# ST_LINK_V3E.net
KiCad netlist of a schematic drawn in Altium Designer
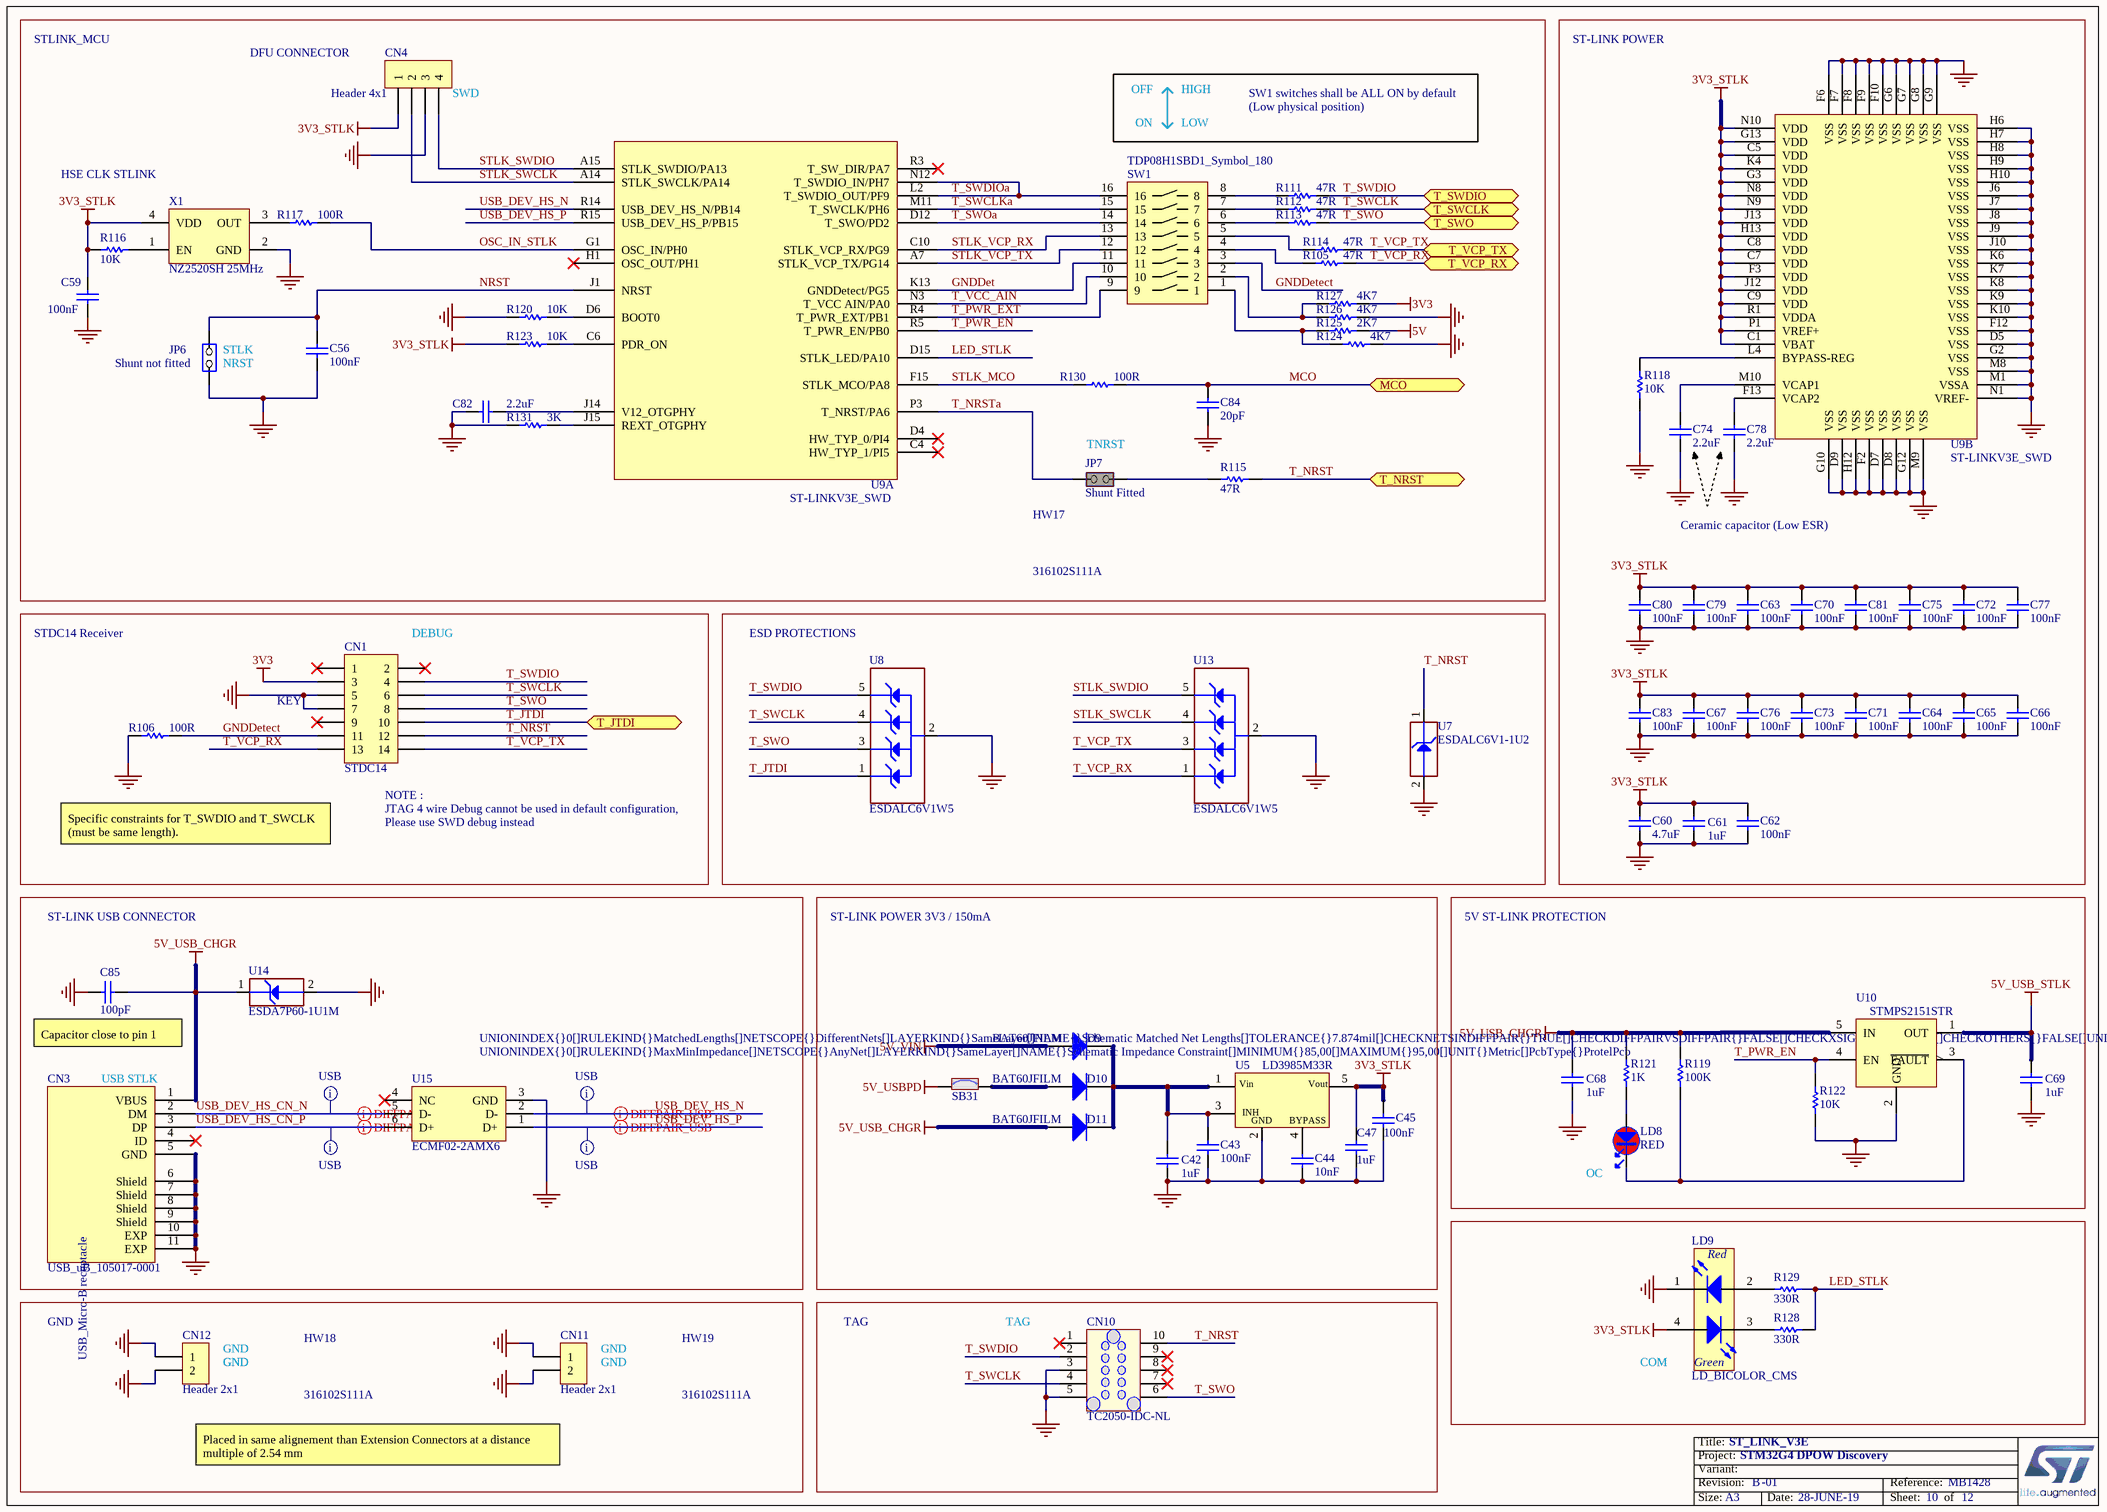
[diagram p0: ST_LINK_V3E.SchDoc]

(export (version "E")
  (design (tool "Eeschema 10.0.6"))
  (components
    (comp (ref "C42")
      (value "1uF")
      (footprint "C0603")
      (description "Capacitor, MLCC, 1uF, 16V, X5R, 10%, 0603, T=0,8mm")
      (fields
        (field (name "INTERNAL_PART_NUMBER") "MCD-00010")
        (field (name "MANUFACTURER_PART_NUMBER") "CC0603KRX5R7BB105")
        (field (name "PROVIDED_BY") "SUBCO")
      )
      (libsource (lib "MCD_PARTS_database") (part "Capacitor"))
    )
    (comp (ref "C43")
      (value "100nF")
      (footprint "C0402")
      (description "Capacitor, MLCC, 100nF, 16V, X7R, 10%, 0402, T=0,5mm")
      (fields
        (field (name "INTERNAL_PART_NUMBER") "MCD-00102")
        (field (name "MANUFACTURER_PART_NUMBER") "CC0402KRX7R7BB104")
        (field (name "PROVIDED_BY") "SUBCO")
      )
      (libsource (lib "MCD_PARTS_database") (part "Capacitor"))
    )
    (comp (ref "C44")
      (value "10nF")
      (footprint "C0402")
      (description "Capacitor, MLCC, 10nF, 16V, X7R, 10%, 0402, T=0.5mm")
      (fields
        (field (name "INTERNAL_PART_NUMBER") "MCD-00011")
        (field (name "MANUFACTURER_PART_NUMBER") "CC0402KRX7R7BB103")
        (field (name "PROVIDED_BY") "SUBCO")
      )
      (libsource (lib "MCD_PARTS_database") (part "Capacitor"))
    )
    (comp (ref "C45")
      (value "100nF")
      (footprint "C0402")
      (description "Capacitor, MLCC, 100nF, 16V, X7R, 10%, 0402, T=0,5mm")
      (fields
        (field (name "INTERNAL_PART_NUMBER") "MCD-00102")
        (field (name "MANUFACTURER_PART_NUMBER") "CC0402KRX7R7BB104")
        (field (name "PROVIDED_BY") "SUBCO")
      )
      (libsource (lib "MCD_PARTS_database") (part "Capacitor"))
    )
    (comp (ref "C47")
      (value "1uF")
      (footprint "C0603")
      (description "Capacitor, MLCC, 1uF, 16V, X5R, 10%, 0603, T=0,8mm")
      (fields
        (field (name "INTERNAL_PART_NUMBER") "MCD-00010")
        (field (name "MANUFACTURER_PART_NUMBER") "CC0603KRX5R7BB105")
        (field (name "PROVIDED_BY") "SUBCO")
      )
      (libsource (lib "MCD_PARTS_database") (part "Capacitor"))
    )
    (comp (ref "C56")
      (value "100nF")
      (footprint "C0402")
      (description "Capacitor, MLCC, 100nF, 16V, X7R, 10%, 0402, T=0,5mm")
      (fields
        (field (name "INTERNAL_PART_NUMBER") "MCD-00102")
        (field (name "MANUFACTURER_PART_NUMBER") "CC0402KRX7R7BB104")
        (field (name "PROVIDED_BY") "SUBCO")
      )
      (libsource (lib "MCD_PARTS_database") (part "Capacitor"))
    )
    (comp (ref "C59")
      (value "100nF")
      (footprint "C0402")
      (description "Capacitor, MLCC, 100nF, 16V, X7R, 10%, 0402, T=0,5mm")
      (fields
        (field (name "INTERNAL_PART_NUMBER") "MCD-00102")
        (field (name "MANUFACTURER_PART_NUMBER") "CC0402KRX7R7BB104")
        (field (name "PROVIDED_BY") "SUBCO")
      )
      (libsource (lib "MCD_PARTS_database") (part "Capacitor"))
    )
    (comp (ref "C60")
      (value "4.7uF")
      (footprint "C0603")
      (description "Capacitor, MLCC, 4.7uF, 16V, X5R, 10%, 0603, T=0.8mm")
      (fields
        (field (name "INTERNAL_PART_NUMBER") "MCD-00009")
        (field (name "MANUFACTURER_PART_NUMBER") "CC0603KRX5R7BB475")
        (field (name "PROVIDED_BY") "SUBCO")
      )
      (libsource (lib "MCD_PARTS_database") (part "Capacitor"))
    )
    (comp (ref "C61")
      (value "1uF")
      (footprint "C0603")
      (description "Capacitor, MLCC, 1uF, 16V, X5R, 10%, 0603, T=0,8mm")
      (fields
        (field (name "INTERNAL_PART_NUMBER") "MCD-00010")
        (field (name "MANUFACTURER_PART_NUMBER") "CC0603KRX5R7BB105")
        (field (name "PROVIDED_BY") "SUBCO")
      )
      (libsource (lib "MCD_PARTS_database") (part "Capacitor"))
    )
    (comp (ref "C62")
      (value "100nF")
      (footprint "C0402")
      (description "Capacitor, MLCC, 100nF, 16V, X7R, 10%, 0402, T=0,5mm")
      (fields
        (field (name "INTERNAL_PART_NUMBER") "MCD-00102")
        (field (name "MANUFACTURER_PART_NUMBER") "CC0402KRX7R7BB104")
        (field (name "PROVIDED_BY") "SUBCO")
      )
      (libsource (lib "MCD_PARTS_database") (part "Capacitor"))
    )
    (comp (ref "C63")
      (value "100nF")
      (footprint "C0402")
      (description "Capacitor, MLCC, 100nF, 16V, X7R, 10%, 0402, T=0,5mm")
      (fields
        (field (name "INTERNAL_PART_NUMBER") "MCD-00102")
        (field (name "MANUFACTURER_PART_NUMBER") "CC0402KRX7R7BB104")
        (field (name "PROVIDED_BY") "SUBCO")
      )
      (libsource (lib "MCD_PARTS_database") (part "Capacitor"))
    )
    (comp (ref "C64")
      (value "100nF")
      (footprint "C0402")
      (description "Capacitor, MLCC, 100nF, 16V, X7R, 10%, 0402, T=0,5mm")
      (fields
        (field (name "INTERNAL_PART_NUMBER") "MCD-00102")
        (field (name "MANUFACTURER_PART_NUMBER") "CC0402KRX7R7BB104")
        (field (name "PROVIDED_BY") "SUBCO")
      )
      (libsource (lib "MCD_PARTS_database") (part "Capacitor"))
    )
    (comp (ref "C65")
      (value "100nF")
      (footprint "C0402")
      (description "Capacitor, MLCC, 100nF, 16V, X7R, 10%, 0402, T=0,5mm")
      (fields
        (field (name "INTERNAL_PART_NUMBER") "MCD-00102")
        (field (name "MANUFACTURER_PART_NUMBER") "CC0402KRX7R7BB104")
        (field (name "PROVIDED_BY") "SUBCO")
      )
      (libsource (lib "MCD_PARTS_database") (part "Capacitor"))
    )
    (comp (ref "C66")
      (value "100nF")
      (footprint "C0402")
      (description "Capacitor, MLCC, 100nF, 16V, X7R, 10%, 0402, T=0,5mm")
      (fields
        (field (name "INTERNAL_PART_NUMBER") "MCD-00102")
        (field (name "MANUFACTURER_PART_NUMBER") "CC0402KRX7R7BB104")
        (field (name "PROVIDED_BY") "SUBCO")
      )
      (libsource (lib "MCD_PARTS_database") (part "Capacitor"))
    )
    (comp (ref "C67")
      (value "100nF")
      (footprint "C0402")
      (description "Capacitor, MLCC, 100nF, 16V, X7R, 10%, 0402, T=0,5mm")
      (fields
        (field (name "INTERNAL_PART_NUMBER") "MCD-00102")
        (field (name "MANUFACTURER_PART_NUMBER") "CC0402KRX7R7BB104")
        (field (name "PROVIDED_BY") "SUBCO")
      )
      (libsource (lib "MCD_PARTS_database") (part "Capacitor"))
    )
    (comp (ref "C68")
      (value "1uF")
      (footprint "C0603")
      (description "Capacitor, MLCC, 1uF, 16V, X5R, 10%, 0603, T=0,8mm")
      (fields
        (field (name "INTERNAL_PART_NUMBER") "MCD-00010")
        (field (name "MANUFACTURER_PART_NUMBER") "CC0603KRX5R7BB105")
        (field (name "PROVIDED_BY") "SUBCO")
      )
      (libsource (lib "MCD_PARTS_database") (part "Capacitor"))
    )
    (comp (ref "C69")
      (value "1uF")
      (footprint "C0603")
      (description "Capacitor, MLCC, 1uF, 16V, X5R, 10%, 0603, T=0,8mm")
      (fields
        (field (name "INTERNAL_PART_NUMBER") "MCD-00010")
        (field (name "MANUFACTURER_PART_NUMBER") "CC0603KRX5R7BB105")
        (field (name "PROVIDED_BY") "SUBCO")
      )
      (libsource (lib "MCD_PARTS_database") (part "Capacitor"))
    )
    (comp (ref "C70")
      (value "100nF")
      (footprint "C0402")
      (description "Capacitor, MLCC, 100nF, 16V, X7R, 10%, 0402, T=0,5mm")
      (fields
        (field (name "INTERNAL_PART_NUMBER") "MCD-00102")
        (field (name "MANUFACTURER_PART_NUMBER") "CC0402KRX7R7BB104")
        (field (name "PROVIDED_BY") "SUBCO")
      )
      (libsource (lib "MCD_PARTS_database") (part "Capacitor"))
    )
    (comp (ref "C71")
      (value "100nF")
      (footprint "C0402")
      (description "Capacitor, MLCC, 100nF, 16V, X7R, 10%, 0402, T=0,5mm")
      (fields
        (field (name "INTERNAL_PART_NUMBER") "MCD-00102")
        (field (name "MANUFACTURER_PART_NUMBER") "CC0402KRX7R7BB104")
        (field (name "PROVIDED_BY") "SUBCO")
      )
      (libsource (lib "MCD_PARTS_database") (part "Capacitor"))
    )
    (comp (ref "C72")
      (value "100nF")
      (footprint "C0402")
      (description "Capacitor, MLCC, 100nF, 16V, X7R, 10%, 0402, T=0,5mm")
      (fields
        (field (name "INTERNAL_PART_NUMBER") "MCD-00102")
        (field (name "MANUFACTURER_PART_NUMBER") "CC0402KRX7R7BB104")
        (field (name "PROVIDED_BY") "SUBCO")
      )
      (libsource (lib "MCD_PARTS_database") (part "Capacitor"))
    )
    (comp (ref "C73")
      (value "100nF")
      (footprint "C0402")
      (description "Capacitor, MLCC, 100nF, 16V, X7R, 10%, 0402, T=0,5mm")
      (fields
        (field (name "INTERNAL_PART_NUMBER") "MCD-00102")
        (field (name "MANUFACTURER_PART_NUMBER") "CC0402KRX7R7BB104")
        (field (name "PROVIDED_BY") "SUBCO")
      )
      (libsource (lib "MCD_PARTS_database") (part "Capacitor"))
    )
    (comp (ref "C74")
      (value "2.2uF")
      (footprint "C1206_H1P15")
      (description "Capacitor, MLCC, 2.2uF, 16V, X7R, 10%, 1206, T=1,15mm")
      (fields
        (field (name "INTERNAL_PART_NUMBER") "MCD-00008")
        (field (name "MANUFACTURER_PART_NUMBER") "CC1206KKX7R7BB225")
        (field (name "PROVIDED_BY") "SUBCO")
      )
      (libsource (lib "MCD_PARTS_database") (part "Capacitor"))
    )
    (comp (ref "C75")
      (value "100nF")
      (footprint "C0402")
      (description "Capacitor, MLCC, 100nF, 16V, X7R, 10%, 0402, T=0,5mm")
      (fields
        (field (name "INTERNAL_PART_NUMBER") "MCD-00102")
        (field (name "MANUFACTURER_PART_NUMBER") "CC0402KRX7R7BB104")
        (field (name "PROVIDED_BY") "SUBCO")
      )
      (libsource (lib "MCD_PARTS_database") (part "Capacitor"))
    )
    (comp (ref "C76")
      (value "100nF")
      (footprint "C0402")
      (description "Capacitor, MLCC, 100nF, 16V, X7R, 10%, 0402, T=0,5mm")
      (fields
        (field (name "INTERNAL_PART_NUMBER") "MCD-00102")
        (field (name "MANUFACTURER_PART_NUMBER") "CC0402KRX7R7BB104")
        (field (name "PROVIDED_BY") "SUBCO")
      )
      (libsource (lib "MCD_PARTS_database") (part "Capacitor"))
    )
    (comp (ref "C77")
      (value "100nF")
      (footprint "C0402")
      (description "Capacitor, MLCC, 100nF, 16V, X7R, 10%, 0402, T=0,5mm")
      (fields
        (field (name "INTERNAL_PART_NUMBER") "MCD-00102")
        (field (name "MANUFACTURER_PART_NUMBER") "CC0402KRX7R7BB104")
        (field (name "PROVIDED_BY") "SUBCO")
      )
      (libsource (lib "MCD_PARTS_database") (part "Capacitor"))
    )
    (comp (ref "C78")
      (value "2.2uF")
      (footprint "C1206_H1P15")
      (description "Capacitor, MLCC, 2.2uF, 16V, X7R, 10%, 1206, T=1,15mm")
      (fields
        (field (name "INTERNAL_PART_NUMBER") "MCD-00008")
        (field (name "MANUFACTURER_PART_NUMBER") "CC1206KKX7R7BB225")
        (field (name "PROVIDED_BY") "SUBCO")
      )
      (libsource (lib "MCD_PARTS_database") (part "Capacitor"))
    )
    (comp (ref "C79")
      (value "100nF")
      (footprint "C0402")
      (description "Capacitor, MLCC, 100nF, 16V, X7R, 10%, 0402, T=0,5mm")
      (fields
        (field (name "INTERNAL_PART_NUMBER") "MCD-00102")
        (field (name "MANUFACTURER_PART_NUMBER") "CC0402KRX7R7BB104")
        (field (name "PROVIDED_BY") "SUBCO")
      )
      (libsource (lib "MCD_PARTS_database") (part "Capacitor"))
    )
    (comp (ref "C80")
      (value "100nF")
      (footprint "C0402")
      (description "Capacitor, MLCC, 100nF, 16V, X7R, 10%, 0402, T=0,5mm")
      (fields
        (field (name "INTERNAL_PART_NUMBER") "MCD-00102")
        (field (name "MANUFACTURER_PART_NUMBER") "CC0402KRX7R7BB104")
        (field (name "PROVIDED_BY") "SUBCO")
      )
      (libsource (lib "MCD_PARTS_database") (part "Capacitor"))
    )
    (comp (ref "C81")
      (value "100nF")
      (footprint "C0402")
      (description "Capacitor, MLCC, 100nF, 16V, X7R, 10%, 0402, T=0,5mm")
      (fields
        (field (name "INTERNAL_PART_NUMBER") "MCD-00102")
        (field (name "MANUFACTURER_PART_NUMBER") "CC0402KRX7R7BB104")
        (field (name "PROVIDED_BY") "SUBCO")
      )
      (libsource (lib "MCD_PARTS_database") (part "Capacitor"))
    )
    (comp (ref "C82")
      (value "2.2uF")
      (footprint "C0603")
      (description "Capacitor, MLCC, 2.2uF, 10V, X5R, 10%, 0603, T=0,8mm")
      (fields
        (field (name "INTERNAL_PART_NUMBER") "MCD-00012")
        (field (name "MANUFACTURER_PART_NUMBER") "CC0603KRX5R6BB225")
        (field (name "PROVIDED_BY") "SUBCO")
      )
      (libsource (lib "MCD_PARTS_database") (part "Capacitor"))
    )
    (comp (ref "C83")
      (value "100nF")
      (footprint "C0402")
      (description "Capacitor, MLCC, 100nF, 16V, X7R, 10%, 0402, T=0,5mm")
      (fields
        (field (name "INTERNAL_PART_NUMBER") "MCD-00102")
        (field (name "MANUFACTURER_PART_NUMBER") "CC0402KRX7R7BB104")
        (field (name "PROVIDED_BY") "SUBCO")
      )
      (libsource (lib "MCD_PARTS_database") (part "Capacitor"))
    )
    (comp (ref "C84")
      (value "20pF")
      (footprint "C0402")
      (description "Capacitor, MLCC, 20pF, 50V, NPO, 5%, 0402, T=0,5mm")
      (fields
        (field (name "INTERNAL_PART_NUMBER") "MCD-00016")
        (field (name "MANUFACTURER_PART_NUMBER") "CC0402JRNPO9BN200")
        (field (name "PROVIDED_BY") "SUBCO")
      )
      (libsource (lib "MCD_PARTS_database") (part "Capacitor"))
    )
    (comp (ref "C85")
      (value "100pF")
      (footprint "C0402")
      (description "Capacitor, MLCC, 100pF, 50V, NPO, 5%, 0402, T=0,5mm")
      (fields
        (field (name "INTERNAL_PART_NUMBER") "MCD-00205")
        (field (name "MANUFACTURER_PART_NUMBER") "CC0402JRNPO9BN101")
        (field (name "PROVIDED_BY") "SUBCO")
      )
      (libsource (lib "MCD_PARTS_database") (part "Capacitor"))
    )
    (comp (ref "CN1")
      (value "STDC14")
      (footprint "CON_STDC14_Receiver_MEDIUM")
      (fields
        (field (name "INTERNAL_PART_NUMBER") "MCD-00592")
        (field (name "MANUFACTURER_PART_NUMBER") "FTSH-107-01-L-DV-K")
        (field (name "MANUFACTURER") "SAMTEC")
        (field (name "PROVIDED_BY") "SUBCO")
      )
      (libsource (lib "MCD_PARTS_database") (part "Header 7x2"))
    )
    (comp (ref "CN3")
      (value "USB_uB_105017-0001")
      (footprint "CON_USBMICROB_MOLEX_105017-0001_H2P90")
      (description "USB-MICRO-B, 0.65mm, RA, SMT, Bottom Mount,")
      (fields
        (field (name "INTERNAL_PART_NUMBER") "MCD-00028")
        (field (name "MANUFACTURER_PART_NUMBER") "1050170001")
        (field (name "PROVIDED_BY") "SUBCO")
      )
      (libsource (lib "MCD_PARTS_database") (part "USB_uB_105017.0001"))
    )
    (comp (ref "CN4")
      (value "Header 4x1")
      (footprint "CON_SAMTEC_TSW-104-07-G-S")
      (description "Header, 4x1, 2,54mm, VR, TH, Height 5.84mm/2.54mm")
      (fields
        (field (name "INTERNAL_PART_NUMBER") "MCD-00029")
        (field (name "MANUFACTURER_PART_NUMBER") "TSW-104-07-x-S")
        (field (name "PROVIDED_BY") "SUBCO")
      )
      (libsource (lib "MCD_PARTS_database") (part "Header 4x1"))
    )
    (comp (ref "CN10")
      (value "TC2050-IDC-NL")
      (footprint "CON_TAG-C_TC2050-IDC-NL")
      (description "Tag_Connector Header, 10x2, No legs")
      (fields
        (field (name "INTERNAL_PART_NUMBER") "MCD-00031")
        (field (name "MANUFACTURER_PART_NUMBER") "TC2050-IDC-NL-FP")
        (field (name "PROVIDED_BY") "SUBCO")
      )
      (libsource (lib "MCD_PARTS_database") (part "Tag-10-C"))
    )
    (comp (ref "CN11")
      (value "Header 2x1")
      (footprint "CON_LYCONN_313102S141346")
      (description "Header 2x1, 2.54mm, VR, TH, height 5.84mm/5.08 mm, height total 13.46 mm")
      (fields
        (field (name "INTERNAL_PART_NUMBER") "MCD-01668")
        (field (name "MANUFACTURER_PART_NUMBER") "313102S141346")
        (field (name "PROVIDED_BY") "SUBCO")
      )
      (libsource (lib "MCD_PARTS_database") (part "Header 2x1"))
    )
    (comp (ref "CN12")
      (value "Header 2x1")
      (footprint "CON_LYCONN_313102S141346")
      (description "Header 2x1, 2.54mm, VR, TH, height 5.84mm/5.08 mm, height total 13.46 mm")
      (fields
        (field (name "INTERNAL_PART_NUMBER") "MCD-01668")
        (field (name "MANUFACTURER_PART_NUMBER") "313102S141346")
        (field (name "PROVIDED_BY") "SUBCO")
      )
      (libsource (lib "MCD_PARTS_database") (part "Header 2x1"))
    )
    (comp (ref "D9")
      (value "BAT60JFILM")
      (footprint "DIO_SOD323")
      (fields
        (field (name "INTERNAL_PART_NUMBER") "MCD-00034")
        (field (name "MANUFACTURER") "STMICROELECTRONICS")
        (field (name "BMS_PART_NUMBER") "9151097")
        (field (name "PROVIDED_BY") "SUBCO with ST control")
      )
      (libsource (lib "MCD_PARTS_database") (part "BAT60JFILM"))
    )
    (comp (ref "D10")
      (value "BAT60JFILM")
      (footprint "DIO_SOD323")
      (fields
        (field (name "INTERNAL_PART_NUMBER") "MCD-00034")
        (field (name "MANUFACTURER") "STMICROELECTRONICS")
        (field (name "BMS_PART_NUMBER") "9151097")
        (field (name "PROVIDED_BY") "SUBCO with ST control")
      )
      (libsource (lib "MCD_PARTS_database") (part "BAT60JFILM"))
    )
    (comp (ref "D11")
      (value "BAT60JFILM")
      (footprint "DIO_SOD323")
      (fields
        (field (name "INTERNAL_PART_NUMBER") "MCD-00034")
        (field (name "MANUFACTURER") "STMICROELECTRONICS")
        (field (name "BMS_PART_NUMBER") "9151097")
        (field (name "PROVIDED_BY") "SUBCO with ST control")
      )
      (libsource (lib "MCD_PARTS_database") (part "BAT60JFILM"))
    )
    (comp (ref "HW17")
      (value "316102S111A")
      (description "Jumper, height 6mm, Black, 2.54mm, 3A, 20 mohm, open")
      (fields
        (field (name "INTERNAL_PART_NUMBER") "MCD-01849")
        (field (name "MANUFACTURER") "JIUBABA")
        (field (name "PROVIDED_BY") "SUBCO")
      )
      (libsource (lib "MCD_PARTS_database") (part "JUMPER_OPEN"))
    )
    (comp (ref "HW18")
      (value "316102S111A")
      (description "Jumper, height 6mm, Black, 2.54mm, 3A, 20 mohm, open")
      (fields
        (field (name "INTERNAL_PART_NUMBER") "MCD-01849")
        (field (name "MANUFACTURER") "JIUBABA")
        (field (name "PROVIDED_BY") "SUBCO")
      )
      (libsource (lib "MCD_PARTS_database") (part "JUMPER_OPEN"))
    )
    (comp (ref "HW19")
      (value "316102S111A")
      (description "Jumper, height 6mm, Black, 2.54mm, 3A, 20 mohm, open")
      (fields
        (field (name "INTERNAL_PART_NUMBER") "MCD-01849")
        (field (name "MANUFACTURER") "JIUBABA")
        (field (name "PROVIDED_BY") "SUBCO")
      )
      (libsource (lib "MCD_PARTS_database") (part "JUMPER_OPEN"))
    )
    (comp (ref "JP6")
      (value "Shunt not fitted")
      (footprint "CON_988-JIUBABA_313102S111116")
      (description "Header 2x1, 2.54mm, VR, TH, height 6 mm / 3 mm, total 11.6mm - Shunt not Fitted by default")
      (fields
        (field (name "INTERNAL_PART_NUMBER") "MCD-01660")
        (field (name "MANUFACTURER_PART_NUMBER") "313102S111116")
        (field (name "PROVIDED_BY") "SUBCO")
      )
      (libsource (lib "MCD_PARTS_database") (part "Jumper_Header 2x1"))
    )
    (comp (ref "JP7")
      (value "Shunt Fitted")
      (footprint "CON_988-JIUBABA_313102S111116")
      (description "Header 2x1, 2.54mm, VR, TH, height 6 mm / 3 mm, total 11.6mm - Shunt Fitted by default")
      (fields
        (field (name "INTERNAL_PART_NUMBER") "MCD-01662")
        (field (name "MANUFACTURER_PART_NUMBER") "313102S111116")
        (field (name "PROVIDED_BY") "SUBCO")
      )
      (libsource (lib "MCD_PARTS_database") (part "Jumper_Header 2x1 Fitted"))
    )
    (comp (ref "LD8")
      (value "RED")
      (footprint "LED_0603_RED")
      (description "LED, Red, 0603")
      (fields
        (field (name "INTERNAL_PART_NUMBER") "MCD-00049")
        (field (name "MANUFACTURER_PART_NUMBER") "19-213-R6C-AP1Q2B/3T")
        (field (name "PROVIDED_BY") "SUBCO")
      )
      (libsource (lib "MCD_PARTS_database") (part "LED_red"))
    )
    (comp (ref "LD9")
      (value "LD_BICOLOR_CMS")
      (footprint "LED_BI-GR_HSMF-A201-A00J1")
      (description "LED Bicolor")
      (fields
        (field (name "INTERNAL_PART_NUMBER") "MCD-00051")
        (field (name "MANUFACTURER_PART_NUMBER") "HSMF-A201-A00J1")
        (field (name "PROVIDED_BY") "SUBCO")
      )
      (libsource (lib "MCD_PARTS_database") (part "LD_BICOLOR_CMS"))
    )
    (comp (ref "R105")
      (value "47R")
      (footprint "R0402")
      (description "Resistor,47R,0402,1%,1/16W")
      (fields
        (field (name "INTERNAL_PART_NUMBER") "MCD-00481")
        (field (name "MANUFACTURER_PART_NUMBER") "RC0402FR-0747RL")
        (field (name "PROVIDED_BY") "SUBCO")
      )
      (libsource (lib "MCD_PARTS_database") (part "Resistor"))
    )
    (comp (ref "R106")
      (value "100R")
      (footprint "R0402")
      (description "Resistor,100R,0402,1%,1/16W")
      (fields
        (field (name "INTERNAL_PART_NUMBER") "MCD-00119")
        (field (name "MANUFACTURER_PART_NUMBER") "RC0402FR-07100RL")
        (field (name "PROVIDED_BY") "SUBCO")
      )
      (libsource (lib "MCD_PARTS_database") (part "Resistor"))
    )
    (comp (ref "R111")
      (value "47R")
      (footprint "R0402")
      (description "Resistor,47R,0402,1%,1/16W")
      (fields
        (field (name "INTERNAL_PART_NUMBER") "MCD-00481")
        (field (name "MANUFACTURER_PART_NUMBER") "RC0402FR-0747RL")
        (field (name "PROVIDED_BY") "SUBCO")
      )
      (libsource (lib "MCD_PARTS_database") (part "Resistor"))
    )
    (comp (ref "R112")
      (value "47R")
      (footprint "R0402")
      (description "Resistor,47R,0402,1%,1/16W")
      (fields
        (field (name "INTERNAL_PART_NUMBER") "MCD-00481")
        (field (name "MANUFACTURER_PART_NUMBER") "RC0402FR-0747RL")
        (field (name "PROVIDED_BY") "SUBCO")
      )
      (libsource (lib "MCD_PARTS_database") (part "Resistor"))
    )
    (comp (ref "R113")
      (value "47R")
      (footprint "R0402")
      (description "Resistor,47R,0402,1%,1/16W")
      (fields
        (field (name "INTERNAL_PART_NUMBER") "MCD-00481")
        (field (name "MANUFACTURER_PART_NUMBER") "RC0402FR-0747RL")
        (field (name "PROVIDED_BY") "SUBCO")
      )
      (libsource (lib "MCD_PARTS_database") (part "Resistor"))
    )
    (comp (ref "R114")
      (value "47R")
      (footprint "R0402")
      (description "Resistor,47R,0402,1%,1/16W")
      (fields
        (field (name "INTERNAL_PART_NUMBER") "MCD-00481")
        (field (name "MANUFACTURER_PART_NUMBER") "RC0402FR-0747RL")
        (field (name "PROVIDED_BY") "SUBCO")
      )
      (libsource (lib "MCD_PARTS_database") (part "Resistor"))
    )
    (comp (ref "R115")
      (value "47R")
      (footprint "R0402")
      (description "Resistor,47R,0402,1%,1/16W")
      (fields
        (field (name "INTERNAL_PART_NUMBER") "MCD-00481")
        (field (name "MANUFACTURER_PART_NUMBER") "RC0402FR-0747RL")
        (field (name "PROVIDED_BY") "SUBCO")
      )
      (libsource (lib "MCD_PARTS_database") (part "Resistor"))
    )
    (comp (ref "R116")
      (value "10K")
      (footprint "R0402")
      (description "Resistor,10K,0402,1%,1/16W")
      (fields
        (field (name "INTERNAL_PART_NUMBER") "MCD-00053")
        (field (name "MANUFACTURER_PART_NUMBER") "RC0402FR-0710KL")
        (field (name "PROVIDED_BY") "SUBCO")
      )
      (libsource (lib "MCD_PARTS_database") (part "Resistor"))
    )
    (comp (ref "R117")
      (value "100R")
      (footprint "R0402")
      (description "Resistor,100R,0402,1%,1/16W")
      (fields
        (field (name "INTERNAL_PART_NUMBER") "MCD-00119")
        (field (name "MANUFACTURER_PART_NUMBER") "RC0402FR-07100RL")
        (field (name "PROVIDED_BY") "SUBCO")
      )
      (libsource (lib "MCD_PARTS_database") (part "Resistor"))
    )
    (comp (ref "R118")
      (value "10K")
      (footprint "R0402")
      (description "Resistor,10K,0402,1%,1/16W")
      (fields
        (field (name "INTERNAL_PART_NUMBER") "MCD-00053")
        (field (name "MANUFACTURER_PART_NUMBER") "RC0402FR-0710KL")
        (field (name "PROVIDED_BY") "SUBCO")
      )
      (libsource (lib "MCD_PARTS_database") (part "Resistor"))
    )
    (comp (ref "R119")
      (value "100K")
      (footprint "R0603")
      (description "Resistor,100K,0603,1%,1/10W")
      (fields
        (field (name "INTERNAL_PART_NUMBER") "MCD-00223")
        (field (name "MANUFACTURER_PART_NUMBER") "RC0603FR-07100KL")
        (field (name "PROVIDED_BY") "SUBCO")
      )
      (libsource (lib "MCD_PARTS_database") (part "Resistor"))
    )
    (comp (ref "R120")
      (value "10K")
      (footprint "R0402")
      (description "Resistor,10K,0402,1%,1/16W")
      (fields
        (field (name "INTERNAL_PART_NUMBER") "MCD-00053")
        (field (name "MANUFACTURER_PART_NUMBER") "RC0402FR-0710KL")
        (field (name "PROVIDED_BY") "SUBCO")
      )
      (libsource (lib "MCD_PARTS_database") (part "Resistor"))
    )
    (comp (ref "R121")
      (value "1K")
      (footprint "R0603")
      (description "Resistor,1K,0603,1%,1/10W")
      (fields
        (field (name "INTERNAL_PART_NUMBER") "MCD-00070")
        (field (name "MANUFACTURER_PART_NUMBER") "RC0603FR-071KL")
        (field (name "PROVIDED_BY") "SUBCO")
      )
      (libsource (lib "MCD_PARTS_database") (part "Resistor"))
    )
    (comp (ref "R122")
      (value "10K")
      (footprint "R0603")
      (description "Resistor,10K,0603,1%,1/10W")
      (fields
        (field (name "INTERNAL_PART_NUMBER") "MCD-00220")
        (field (name "MANUFACTURER_PART_NUMBER") "RC0603FR-0710KL")
        (field (name "PROVIDED_BY") "SUBCO")
      )
      (libsource (lib "MCD_PARTS_database") (part "Resistor"))
    )
    (comp (ref "R123")
      (value "10K")
      (footprint "R0402")
      (description "Resistor,10K,0402,1%,1/16W")
      (fields
        (field (name "INTERNAL_PART_NUMBER") "MCD-00053")
        (field (name "MANUFACTURER_PART_NUMBER") "RC0402FR-0710KL")
        (field (name "PROVIDED_BY") "SUBCO")
      )
      (libsource (lib "MCD_PARTS_database") (part "Resistor"))
    )
    (comp (ref "R124")
      (value "4K7")
      (footprint "R0402")
      (description "Resistor,4K7,0402,1%,1/16W")
      (fields
        (field (name "INTERNAL_PART_NUMBER") "MCD-00065")
        (field (name "MANUFACTURER_PART_NUMBER") "RC0402FR-074K7L")
        (field (name "PROVIDED_BY") "SUBCO")
      )
      (libsource (lib "MCD_PARTS_database") (part "Resistor"))
    )
    (comp (ref "R125")
      (value "2K7")
      (footprint "R0402")
      (description "Resistor,2K7,0402,1%,1/16W")
      (fields
        (field (name "INTERNAL_PART_NUMBER") "MCD-00055")
        (field (name "MANUFACTURER_PART_NUMBER") "RC0402FR-072K7L")
        (field (name "PROVIDED_BY") "SUBCO")
      )
      (libsource (lib "MCD_PARTS_database") (part "Resistor"))
    )
    (comp (ref "R126")
      (value "4K7")
      (footprint "R0402")
      (description "Resistor,4K7,0402,1%,1/16W")
      (fields
        (field (name "INTERNAL_PART_NUMBER") "MCD-00065")
        (field (name "MANUFACTURER_PART_NUMBER") "RC0402FR-074K7L")
        (field (name "PROVIDED_BY") "SUBCO")
      )
      (libsource (lib "MCD_PARTS_database") (part "Resistor"))
    )
    (comp (ref "R127")
      (value "4K7")
      (footprint "R0402")
      (description "Resistor,4K7,0402,1%,1/16W")
      (fields
        (field (name "INTERNAL_PART_NUMBER") "MCD-00065")
        (field (name "MANUFACTURER_PART_NUMBER") "RC0402FR-074K7L")
        (field (name "PROVIDED_BY") "SUBCO")
      )
      (libsource (lib "MCD_PARTS_database") (part "Resistor"))
    )
    (comp (ref "R128")
      (value "330R")
      (footprint "R0603")
      (description "Resistor,330R,0603,1%,1/10W")
      (fields
        (field (name "INTERNAL_PART_NUMBER") "MCD-00197")
        (field (name "MANUFACTURER_PART_NUMBER") "RC0603FR-07330RL")
        (field (name "PROVIDED_BY") "SUBCO")
      )
      (libsource (lib "MCD_PARTS_database") (part "Resistor"))
    )
    (comp (ref "R129")
      (value "330R")
      (footprint "R0603")
      (description "Resistor,330R,0603,1%,1/10W")
      (fields
        (field (name "INTERNAL_PART_NUMBER") "MCD-00197")
        (field (name "MANUFACTURER_PART_NUMBER") "RC0603FR-07330RL")
        (field (name "PROVIDED_BY") "SUBCO")
      )
      (libsource (lib "MCD_PARTS_database") (part "Resistor"))
    )
    (comp (ref "R130")
      (value "100R")
      (footprint "R0402")
      (description "Resistor,100R,0402,1%,1/16W")
      (fields
        (field (name "INTERNAL_PART_NUMBER") "MCD-00119")
        (field (name "MANUFACTURER_PART_NUMBER") "RC0402FR-07100RL")
        (field (name "PROVIDED_BY") "SUBCO")
      )
      (libsource (lib "MCD_PARTS_database") (part "Resistor"))
    )
    (comp (ref "R131")
      (value "3K")
      (footprint "R0402")
      (description "Resistor,3K,0402,1%,1/16W")
      (fields
        (field (name "INTERNAL_PART_NUMBER") "MCD-00185")
        (field (name "MANUFACTURER_PART_NUMBER") "RC0402FR-073KL")
        (field (name "PROVIDED_BY") "SUBCO")
      )
      (libsource (lib "MCD_PARTS_database") (part "Resistor"))
    )
    (comp (ref "SB31")
      (value "SB_ON")
      (footprint "SOLDER-BRIDGE_R0603-0R")
      (description "Solder Bridge ON")
      (fields
        (field (name "INTERNAL_PART_NUMBER") "MCD-00071")
        (field (name "MANUFACTURER_PART_NUMBER") "RC0603JR-070RL")
        (field (name "PROVIDED_BY") "SUBCO")
      )
      (libsource (lib "MCD_PARTS_database") (part "SB_ON"))
    )
    (comp (ref "SW1")
      (value "TDP08H1SBD1_Symbol_180")
      (footprint "SWI_C&K_TDP08H1SBD1")
      (description "8 positions, Side Actuated DIP switch, 1.27mm, SMT, height 4.1mm, piano type")
      (fields
        (field (name "INTERNAL_PART_NUMBER") "MCD-01685")
        (field (name "MANUFACTURER_PART_NUMBER") "TDP08H1SBD1")
        (field (name "PROVIDED_BY") "SUBCO")
      )
      (libsource (lib "MCD_PARTS_database") (part "TDP08H1SBD1_180"))
    )
    (comp (ref "U5")
      (value "LD3985M33R")
      (footprint "REG_SOT23-5L")
      (description "Ultra low drop-low noise BiCMOS voltage, regulators low ESR capacitors compatible")
      (fields
        (field (name "INTERNAL_PART_NUMBER") "MCD-00086")
        (field (name "MANUFACTURER") "STMICROELECTRONICS")
        (field (name "PROVIDED_BY") "SUBCO with ST control")
      )
      (libsource (lib "MCD_PARTS_database") (part "LD3985M33R"))
    )
    (comp (ref "U7")
      (value "ESDALC6V1-1U2")
      (footprint "ESD_ST0201")
      (description "ESD protection 6V1")
      (fields
        (field (name "INTERNAL_PART_NUMBER") "MCD-00170")
        (field (name "MANUFACTURER") "STMICROELECTRONICS")
        (field (name "PROVIDED_BY") "SUBCO with ST control")
      )
      (libsource (lib "") (part "ESD-TRANSIL_1"))
    )
    (comp (ref "U8")
      (value "ESDALC6V1W5")
      (footprint "ESD_SOT323-5L")
      (description "Dual Transil array for ESD protection")
      (fields
        (field (name "INTERNAL_PART_NUMBER") "MCD-00136")
        (field (name "MANUFACTURER") "STMICROELECTRONICS")
        (field (name "PROVIDED_BY") "SUBCO with ST control")
      )
      (libsource (lib "MCD_PARTS_database") (part "ESDALC6V1W5"))
    )
    (comp (ref "U9")
      (value "ST-LINKV3E_SWD")
      (footprint "ICC_UFBGA201_176+25_10X10_P065")
      (description "STM32F723IEK  (STM32F7) BGA176")
      (fields
        (field (name "INTERNAL_PART_NUMBER") "MCD-00596")
        (field (name "MANUFACTURER_PART_NUMBER") "STM32F723IEK6")
        (field (name "PROVIDED_BY") "SUBCO with ST control")
      )
      (libsource (lib "MCD_PARTS_database") (part "ST-LINKV3E_SWD"))
    )
    (comp (ref "U10")
      (value "STMPS2151STR")
      (footprint "MOS_SOT23-5L")
      (description "500mA, Enhanced single channel power switches with active high enable pin")
      (fields
        (field (name "INTERNAL_PART_NUMBER") "MCD-00159")
        (field (name "MANUFACTURER") "STMICROELECTRONICS")
        (field (name "PROVIDED_BY") "SUBCO with ST control")
      )
      (libsource (lib "MCD_PARTS_database") (part "STMPS2151STR"))
    )
    (comp (ref "U13")
      (value "ESDALC6V1W5")
      (footprint "ESD_SOT323-5L")
      (description "Dual Transil array for ESD protection")
      (fields
        (field (name "INTERNAL_PART_NUMBER") "MCD-00136")
        (field (name "MANUFACTURER") "STMICROELECTRONICS")
        (field (name "PROVIDED_BY") "SUBCO with ST control")
      )
      (libsource (lib "MCD_PARTS_database") (part "ESDALC6V1W5"))
    )
    (comp (ref "U14")
      (value "ESDA7P60-1U1M")
      (footprint "ESD_QFN2_1P6X1_P125")
      (description "High power transient voltage suppressor, 7V breakdown")
      (fields
        (field (name "INTERNAL_PART_NUMBER") "MCD-00251")
        (field (name "MANUFACTURER") "STMICROELECTRONICS")
        (field (name "PROVIDED_BY") "SUBCO with ST control")
      )
      (libsource (lib "MCD_PARTS_database") (part "ESD-TRANSIL"))
    )
    (comp (ref "U15")
      (value "ECMF02-2AMX6")
      (footprint "ESD_QFN-6L_1P7X1P5_P050")
      (description "Common mode filter with ESD protection for USB 2.0 interface")
      (fields
        (field (name "INTERNAL_PART_NUMBER") "MCD-00649")
        (field (name "MANUFACTURER") "STMICROELECTRONICS")
        (field (name "PROVIDED_BY") "SUBCO with ST control")
      )
      (libsource (lib "MCD_PARTS_database") (part "ECMF02-2AMX6"))
    )
    (comp (ref "X1")
      (value "NZ2520SH 25MHz")
      (footprint "OSC_NDK_NZ2520SB_4P")
      (description "Oscillator 25Mhz, +-50ppm, Vcc:3.3V typ, square wave: [0.1Vcc;0.9Vcc], Enable pin, SMD")
      (fields
        (field (name "INTERNAL_PART_NUMBER") "MCD-00597")
        (field (name "MANUFACTURER_PART_NUMBER") "NZ2520SH 25MHz END4869C")
        (field (name "PROVIDED_BY") "SUBCO")
      )
      (libsource (lib "MCD_PARTS_database") (part "OSCILLATOR_4_PINS"))
    )
  )
  (nets
    (net (code "1") (name "/GNDDet") (class "Default")
      (node (ref "SW1") (pin "11") (pinfunction "11_11") (pintype "passive"))
      (node (ref "U9") (pin "K13") (pinfunction "GNDDetect/PG5_K13") (pintype "passive"))
    )
    (net (code "2") (name "/GNDDetect") (class "Default")
      (node (ref "CN1") (pin "11") (pinfunction "11_11") (pintype "passive"))
      (node (ref "R106") (pin "2") (pinfunction "2_2") (pintype "passive"))
      (node (ref "SW1") (pin "3") (pinfunction "3_3") (pintype "passive"))
    )
    (net (code "3") (name "/LED_STLK") (class "Default")
      (node (ref "R128") (pin "2") (pinfunction "2_2") (pintype "passive"))
      (node (ref "R129") (pin "2") (pinfunction "2_2") (pintype "passive"))
      (node (ref "U9") (pin "D15") (pinfunction "STLK_LED/PA10_D15") (pintype "passive"))
    )
    (net (code "4") (name "/MCO") (class "Default")
      (node (ref "C84") (pin "2") (pinfunction "2_2") (pintype "passive"))
      (node (ref "R130") (pin "2") (pinfunction "2_2") (pintype "passive"))
    )
    (net (code "5") (name "/NRST") (class "Default")
      (node (ref "C56") (pin "2") (pinfunction "2_2") (pintype "passive"))
      (node (ref "JP6") (pin "2") (pinfunction "NO_2") (pintype "passive"))
      (node (ref "U9") (pin "J1") (pinfunction "NRST_J1") (pintype "passive"))
    )
    (net (code "6") (name "/OSC_IN_STLK") (class "Default")
      (node (ref "R117") (pin "2") (pinfunction "2_2") (pintype "passive"))
      (node (ref "U9") (pin "G1") (pinfunction "OSC_IN/PH0_G1") (pintype "passive"))
    )
    (net (code "7") (name "/STLK_MCO") (class "Default")
      (node (ref "R130") (pin "1") (pinfunction "1_1") (pintype "passive"))
      (node (ref "U9") (pin "F15") (pinfunction "STLK_MCO/PA8_F15") (pintype "passive"))
    )
    (net (code "8") (name "/STLK_SWCLK") (class "Default")
      (node (ref "CN4") (pin "2") (pinfunction "2_2") (pintype "passive"))
      (node (ref "U13") (pin "4") (pinfunction "IO3_4") (pintype "passive"))
      (node (ref "U9") (pin "A14") (pinfunction "STLK_SWCLK/PA14_A14") (pintype "passive"))
    )
    (net (code "9") (name "/STLK_SWDIO") (class "Default")
      (node (ref "CN4") (pin "4") (pinfunction "4_4") (pintype "passive"))
      (node (ref "U13") (pin "5") (pinfunction "IO4_5") (pintype "passive"))
      (node (ref "U9") (pin "A15") (pinfunction "STLK_SWDIO/PA13_A15") (pintype "passive"))
    )
    (net (code "10") (name "/STLK_VCP_RX") (class "Default")
      (node (ref "SW1") (pin "13") (pinfunction "13_13") (pintype "passive"))
      (node (ref "U9") (pin "C10") (pinfunction "STLK_VCP_RX/PG9_C10") (pintype "passive"))
    )
    (net (code "11") (name "/STLK_VCP_TX") (class "Default")
      (node (ref "SW1") (pin "12") (pinfunction "12_12") (pintype "passive"))
      (node (ref "U9") (pin "A7") (pinfunction "STLK_VCP_TX/PG14_A7") (pintype "passive"))
    )
    (net (code "12") (name "/T_JTDI") (class "Default")
      (node (ref "CN1") (pin "10") (pinfunction "10_10") (pintype "passive"))
      (node (ref "U8") (pin "1") (pinfunction "IO1_1") (pintype "passive"))
    )
    (net (code "13") (name "/T_NRST") (class "Default")
      (node (ref "CN1") (pin "12") (pinfunction "12_12") (pintype "passive"))
      (node (ref "CN10") (pin "10") (pinfunction "10_10") (pintype "passive"))
      (node (ref "R115") (pin "2") (pinfunction "2_2") (pintype "passive"))
      (node (ref "U7") (pin "1") (pinfunction "IO1_1") (pintype "passive"))
    )
    (net (code "14") (name "/T_NRSTa") (class "Default")
      (node (ref "JP7") (pin "1") (pinfunction "COMMON_1") (pintype "passive"))
      (node (ref "U9") (pin "P3") (pinfunction "T_NRST/PA6_P3") (pintype "passive"))
    )
    (net (code "15") (name "/T_PWR_EN") (class "Default")
      (node (ref "R122") (pin "1") (pinfunction "1_1") (pintype "passive"))
      (node (ref "U10") (pin "4") (pinfunction "EN_4") (pintype "passive"))
      (node (ref "U9") (pin "R5") (pinfunction "T_PWR_EN/PB0_R5") (pintype "passive"))
    )
    (net (code "16") (name "/T_PWR_EXT") (class "Default")
      (node (ref "SW1") (pin "9") (pinfunction "9_9") (pintype "passive"))
      (node (ref "U9") (pin "R4") (pinfunction "T_PWR_EXT/PB1_R4") (pintype "passive"))
    )
    (net (code "17") (name "/T_SWCLK") (class "Default")
      (node (ref "CN1") (pin "6") (pinfunction "6_6") (pintype "passive"))
      (node (ref "CN10") (pin "4") (pinfunction "4_4") (pintype "passive"))
      (node (ref "R112") (pin "2") (pinfunction "2_2") (pintype "passive"))
      (node (ref "U8") (pin "4") (pinfunction "IO3_4") (pintype "passive"))
    )
    (net (code "18") (name "/T_SWCLKa") (class "Default")
      (node (ref "SW1") (pin "15") (pinfunction "15_15") (pintype "passive"))
      (node (ref "U9") (pin "M11") (pinfunction "T_SWCLK/PH6_M11") (pintype "passive"))
    )
    (net (code "19") (name "/T_SWDIO") (class "Default")
      (node (ref "CN1") (pin "4") (pinfunction "4_4") (pintype "passive"))
      (node (ref "CN10") (pin "2") (pinfunction "2_2") (pintype "passive"))
      (node (ref "R111") (pin "2") (pinfunction "2_2") (pintype "passive"))
      (node (ref "U8") (pin "5") (pinfunction "IO4_5") (pintype "passive"))
    )
    (net (code "20") (name "/T_SWDIOa") (class "Default")
      (node (ref "SW1") (pin "16") (pinfunction "16_16") (pintype "passive"))
      (node (ref "U9") (pin "L2") (pinfunction "T_SWDIO_OUT/PF9_L2") (pintype "passive"))
      (node (ref "U9") (pin "N12") (pinfunction "T_SWDIO_IN/PH7_N12") (pintype "passive"))
    )
    (net (code "21") (name "/T_SWO") (class "Default")
      (node (ref "CN1") (pin "8") (pinfunction "8_8") (pintype "passive"))
      (node (ref "CN10") (pin "6") (pinfunction "6_6") (pintype "passive"))
      (node (ref "R113") (pin "2") (pinfunction "2_2") (pintype "passive"))
      (node (ref "U8") (pin "3") (pinfunction "IO2_3") (pintype "passive"))
    )
    (net (code "22") (name "/T_SWOa") (class "Default")
      (node (ref "SW1") (pin "14") (pinfunction "14_14") (pintype "passive"))
      (node (ref "U9") (pin "D12") (pinfunction "T_SWO/PD2_D12") (pintype "passive"))
    )
    (net (code "23") (name "/T_VCC_AIN") (class "Default")
      (node (ref "SW1") (pin "10") (pinfunction "10_10") (pintype "passive"))
      (node (ref "U9") (pin "N3") (pinfunction "T_VCC_AIN/PA0_N3") (pintype "passive"))
    )
    (net (code "24") (name "/T_VCP_RX") (class "Default")
      (node (ref "CN1") (pin "13") (pinfunction "13_13") (pintype "passive"))
      (node (ref "R105") (pin "2") (pinfunction "2_2") (pintype "passive"))
      (node (ref "U13") (pin "1") (pinfunction "IO1_1") (pintype "passive"))
    )
    (net (code "25") (name "/T_VCP_TX") (class "Default")
      (node (ref "CN1") (pin "14") (pinfunction "14_14") (pintype "passive"))
      (node (ref "R114") (pin "2") (pinfunction "2_2") (pintype "passive"))
      (node (ref "U13") (pin "3") (pinfunction "IO2_3") (pintype "passive"))
    )
    (net (code "26") (name "/USB_DEV_HS_CN_N") (class "Default")
      (node (ref "CN3") (pin "2") (pinfunction "DM_2") (pintype "passive"))
      (node (ref "U15") (pin "5") (pinfunction "D-_5") (pintype "passive"))
    )
    (net (code "27") (name "/USB_DEV_HS_CN_P") (class "Default")
      (node (ref "CN3") (pin "3") (pinfunction "DP_3") (pintype "passive"))
      (node (ref "U15") (pin "6") (pinfunction "D+_6") (pintype "passive"))
    )
    (net (code "28") (name "/USB_DEV_HS_N") (class "Default")
      (node (ref "U15") (pin "2") (pinfunction "D-_2") (pintype "passive"))
      (node (ref "U9") (pin "R14") (pinfunction "USB_DEV_HS_N/PB14_R14") (pintype "passive"))
    )
    (net (code "29") (name "/USB_DEV_HS_P") (class "Default")
      (node (ref "U15") (pin "1") (pinfunction "D+_1") (pintype "passive"))
      (node (ref "U9") (pin "R15") (pinfunction "USB_DEV_HS_P/PB15_R15") (pintype "passive"))
    )
    (net (code "30") (name "3V3") (class "Default")
      (node (ref "CN1") (pin "3") (pinfunction "3_3") (pintype "passive"))
      (node (ref "R127") (pin "2") (pinfunction "2_2") (pintype "passive"))
    )
    (net (code "31") (name "3V3_STLK") (class "Default")
      (node (ref "C45") (pin "2") (pinfunction "2_2") (pintype "passive"))
      (node (ref "C47") (pin "2") (pinfunction "2_2") (pintype "passive"))
      (node (ref "C59") (pin "2") (pinfunction "2_2") (pintype "passive"))
      (node (ref "C60") (pin "2") (pinfunction "2_2") (pintype "passive"))
      (node (ref "C61") (pin "2") (pinfunction "2_2") (pintype "passive"))
      (node (ref "C62") (pin "2") (pinfunction "2_2") (pintype "passive"))
      (node (ref "C63") (pin "2") (pinfunction "2_2") (pintype "passive"))
      (node (ref "C64") (pin "2") (pinfunction "2_2") (pintype "passive"))
      (node (ref "C65") (pin "2") (pinfunction "2_2") (pintype "passive"))
      (node (ref "C66") (pin "2") (pinfunction "2_2") (pintype "passive"))
      (node (ref "C67") (pin "2") (pinfunction "2_2") (pintype "passive"))
      (node (ref "C70") (pin "2") (pinfunction "2_2") (pintype "passive"))
      (node (ref "C71") (pin "2") (pinfunction "2_2") (pintype "passive"))
      (node (ref "C72") (pin "2") (pinfunction "2_2") (pintype "passive"))
      (node (ref "C73") (pin "2") (pinfunction "2_2") (pintype "passive"))
      (node (ref "C75") (pin "2") (pinfunction "2_2") (pintype "passive"))
      (node (ref "C76") (pin "2") (pinfunction "2_2") (pintype "passive"))
      (node (ref "C77") (pin "2") (pinfunction "2_2") (pintype "passive"))
      (node (ref "C79") (pin "2") (pinfunction "2_2") (pintype "passive"))
      (node (ref "C80") (pin "2") (pinfunction "2_2") (pintype "passive"))
      (node (ref "C81") (pin "2") (pinfunction "2_2") (pintype "passive"))
      (node (ref "C83") (pin "2") (pinfunction "2_2") (pintype "passive"))
      (node (ref "CN4") (pin "1") (pinfunction "1_1") (pintype "passive"))
      (node (ref "LD9") (pin "4") (pinfunction "YellowGreen_anode_4") (pintype "passive"))
      (node (ref "R116") (pin "1") (pinfunction "1_1") (pintype "passive"))
      (node (ref "R123") (pin "1") (pinfunction "1_1") (pintype "passive"))
      (node (ref "U5") (pin "5") (pinfunction "Vout_5") (pintype "passive"))
      (node (ref "U9") (pin "C1") (pinfunction "VBAT_C1") (pintype "passive"))
      (node (ref "U9") (pin "C5") (pinfunction "VDD_C5") (pintype "passive"))
      (node (ref "U9") (pin "C7") (pinfunction "VDD_C7") (pintype "passive"))
      (node (ref "U9") (pin "C8") (pinfunction "VDD_C8") (pintype "passive"))
      (node (ref "U9") (pin "C9") (pinfunction "VDD_C9") (pintype "passive"))
      (node (ref "U9") (pin "F3") (pinfunction "VDD_F3") (pintype "passive"))
      (node (ref "U9") (pin "G13") (pinfunction "VDD_G13") (pintype "passive"))
      (node (ref "U9") (pin "G3") (pinfunction "VDD_G3") (pintype "passive"))
      (node (ref "U9") (pin "H13") (pinfunction "VDD_H13") (pintype "passive"))
      (node (ref "U9") (pin "J12") (pinfunction "VDD_J12") (pintype "passive"))
      (node (ref "U9") (pin "J13") (pinfunction "VDD_J13") (pintype "passive"))
      (node (ref "U9") (pin "K4") (pinfunction "VDD_K4") (pintype "passive"))
      (node (ref "U9") (pin "N10") (pinfunction "VDD_N10") (pintype "passive"))
      (node (ref "U9") (pin "N8") (pinfunction "VDD_N8") (pintype "passive"))
      (node (ref "U9") (pin "N9") (pinfunction "VDD_N9") (pintype "passive"))
      (node (ref "U9") (pin "P1") (pinfunction "VREF+_P1") (pintype "passive"))
      (node (ref "U9") (pin "R1") (pinfunction "VDDA_R1") (pintype "passive"))
      (node (ref "X1") (pin "4") (pinfunction "VDD_4") (pintype "passive"))
    )
    (net (code "32") (name "5V") (class "Default")
      (node (ref "R125") (pin "1") (pinfunction "1_1") (pintype "passive"))
    )
    (net (code "33") (name "5V_USBPD") (class "Default")
      (node (ref "SB31") (pin "1") (pinfunction "1_1") (pintype "passive"))
    )
    (net (code "34") (name "5V_USB_CHGR") (class "Default")
      (node (ref "C68") (pin "2") (pinfunction "2_2") (pintype "passive"))
      (node (ref "C85") (pin "2") (pinfunction "2_2") (pintype "passive"))
      (node (ref "CN3") (pin "1") (pinfunction "VBUS_1") (pintype "passive"))
      (node (ref "D11") (pin "1") (pinfunction "A_1") (pintype "passive"))
      (node (ref "R119") (pin "2") (pinfunction "2_2") (pintype "passive"))
      (node (ref "R121") (pin "2") (pinfunction "2_2") (pintype "passive"))
      (node (ref "U10") (pin "5") (pinfunction "IN_5") (pintype "passive"))
      (node (ref "U14") (pin "1") (pinfunction "IO1_1") (pintype "passive"))
    )
    (net (code "35") (name "5V_USB_STLK") (class "Default")
      (node (ref "C69") (pin "2") (pinfunction "2_2") (pintype "passive"))
      (node (ref "U10") (pin "1") (pinfunction "OUT_1") (pintype "passive"))
    )
    (net (code "36") (name "5V_VIN") (class "Default")
      (node (ref "D9") (pin "1") (pinfunction "A_1") (pintype "passive"))
    )
    (net (code "37") (name "GND") (class "Default")
      (node (ref "C42") (pin "1") (pinfunction "1_1") (pintype "passive"))
      (node (ref "C43") (pin "1") (pinfunction "1_1") (pintype "passive"))
      (node (ref "C44") (pin "1") (pinfunction "1_1") (pintype "passive"))
      (node (ref "C45") (pin "1") (pinfunction "1_1") (pintype "passive"))
      (node (ref "C47") (pin "1") (pinfunction "1_1") (pintype "passive"))
      (node (ref "C56") (pin "1") (pinfunction "1_1") (pintype "passive"))
      (node (ref "C59") (pin "1") (pinfunction "1_1") (pintype "passive"))
      (node (ref "C60") (pin "1") (pinfunction "1_1") (pintype "passive"))
      (node (ref "C61") (pin "1") (pinfunction "1_1") (pintype "passive"))
      (node (ref "C62") (pin "1") (pinfunction "1_1") (pintype "passive"))
      (node (ref "C63") (pin "1") (pinfunction "1_1") (pintype "passive"))
      (node (ref "C64") (pin "1") (pinfunction "1_1") (pintype "passive"))
      (node (ref "C65") (pin "1") (pinfunction "1_1") (pintype "passive"))
      (node (ref "C66") (pin "1") (pinfunction "1_1") (pintype "passive"))
      (node (ref "C67") (pin "1") (pinfunction "1_1") (pintype "passive"))
      (node (ref "C68") (pin "1") (pinfunction "1_1") (pintype "passive"))
      (node (ref "C69") (pin "1") (pinfunction "1_1") (pintype "passive"))
      (node (ref "C70") (pin "1") (pinfunction "1_1") (pintype "passive"))
      (node (ref "C71") (pin "1") (pinfunction "1_1") (pintype "passive"))
      (node (ref "C72") (pin "1") (pinfunction "1_1") (pintype "passive"))
      (node (ref "C73") (pin "1") (pinfunction "1_1") (pintype "passive"))
      (node (ref "C74") (pin "1") (pinfunction "1_1") (pintype "passive"))
      (node (ref "C75") (pin "1") (pinfunction "1_1") (pintype "passive"))
      (node (ref "C76") (pin "1") (pinfunction "1_1") (pintype "passive"))
      (node (ref "C77") (pin "1") (pinfunction "1_1") (pintype "passive"))
      (node (ref "C78") (pin "1") (pinfunction "1_1") (pintype "passive"))
      (node (ref "C79") (pin "1") (pinfunction "1_1") (pintype "passive"))
      (node (ref "C80") (pin "1") (pinfunction "1_1") (pintype "passive"))
      (node (ref "C81") (pin "1") (pinfunction "1_1") (pintype "passive"))
      (node (ref "C82") (pin "1") (pinfunction "1_1") (pintype "passive"))
      (node (ref "C83") (pin "1") (pinfunction "1_1") (pintype "passive"))
      (node (ref "C84") (pin "1") (pinfunction "1_1") (pintype "passive"))
      (node (ref "C85") (pin "1") (pinfunction "1_1") (pintype "passive"))
      (node (ref "CN1") (pin "5") (pinfunction "5_5") (pintype "passive"))
      (node (ref "CN1") (pin "7") (pinfunction "7_7") (pintype "passive"))
      (node (ref "CN10") (pin "3") (pinfunction "3_3") (pintype "passive"))
      (node (ref "CN10") (pin "5") (pinfunction "5_5") (pintype "passive"))
      (node (ref "CN11") (pin "1") (pinfunction "1_1") (pintype "passive"))
      (node (ref "CN11") (pin "2") (pinfunction "2_2") (pintype "passive"))
      (node (ref "CN12") (pin "1") (pinfunction "1_1") (pintype "passive"))
      (node (ref "CN12") (pin "2") (pinfunction "2_2") (pintype "passive"))
      (node (ref "CN3") (pin "10") (pinfunction "EXP_10") (pintype "passive"))
      (node (ref "CN3") (pin "11") (pinfunction "EXP_11") (pintype "passive"))
      (node (ref "CN3") (pin "5") (pinfunction "GND_5") (pintype "passive"))
      (node (ref "CN3") (pin "6") (pinfunction "Shield_6") (pintype "passive"))
      (node (ref "CN3") (pin "7") (pinfunction "Shield_7") (pintype "passive"))
      (node (ref "CN3") (pin "8") (pinfunction "Shield_8") (pintype "passive"))
      (node (ref "CN3") (pin "9") (pinfunction "Shield_9") (pintype "passive"))
      (node (ref "CN4") (pin "3") (pinfunction "3_3") (pintype "passive"))
      (node (ref "JP6") (pin "1") (pinfunction "COMMON_1") (pintype "passive"))
      (node (ref "LD9") (pin "1") (pinfunction "RED_cathode_1") (pintype "passive"))
      (node (ref "R106") (pin "1") (pinfunction "1_1") (pintype "passive"))
      (node (ref "R118") (pin "1") (pinfunction "1_1") (pintype "passive"))
      (node (ref "R120") (pin "1") (pinfunction "1_1") (pintype "passive"))
      (node (ref "R122") (pin "2") (pinfunction "2_2") (pintype "passive"))
      (node (ref "R124") (pin "1") (pinfunction "1_1") (pintype "passive"))
      (node (ref "R126") (pin "2") (pinfunction "2_2") (pintype "passive"))
      (node (ref "R131") (pin "1") (pinfunction "1_1") (pintype "passive"))
      (node (ref "U10") (pin "2") (pinfunction "GND_2") (pintype "passive"))
      (node (ref "U13") (pin "2") (pinfunction "GND_2") (pintype "passive"))
      (node (ref "U14") (pin "2") (pinfunction "GND_2") (pintype "passive"))
      (node (ref "U15") (pin "3") (pinfunction "GND_3") (pintype "passive"))
      (node (ref "U5") (pin "2") (pinfunction "GND_2") (pintype "passive"))
      (node (ref "U7") (pin "2") (pinfunction "GND_2") (pintype "passive"))
      (node (ref "U8") (pin "2") (pinfunction "GND_2") (pintype "passive"))
      (node (ref "U9") (pin "D5") (pinfunction "VSS_D5") (pintype "passive"))
      (node (ref "U9") (pin "D7") (pinfunction "VSS_D7") (pintype "passive"))
      (node (ref "U9") (pin "D8") (pinfunction "VSS_D8") (pintype "passive"))
      (node (ref "U9") (pin "D9") (pinfunction "VSS_D9") (pintype "passive"))
      (node (ref "U9") (pin "F10") (pinfunction "VSS_F10") (pintype "passive"))
      (node (ref "U9") (pin "F12") (pinfunction "VSS_F12") (pintype "passive"))
      (node (ref "U9") (pin "F2") (pinfunction "VSS_F2") (pintype "passive"))
      (node (ref "U9") (pin "F6") (pinfunction "VSS_F6") (pintype "passive"))
      (node (ref "U9") (pin "F7") (pinfunction "VSS_F7") (pintype "passive"))
      (node (ref "U9") (pin "F8") (pinfunction "VSS_F8") (pintype "passive"))
      (node (ref "U9") (pin "F9") (pinfunction "VSS_F9") (pintype "passive"))
      (node (ref "U9") (pin "G10") (pinfunction "VSS_G10") (pintype "passive"))
      (node (ref "U9") (pin "G12") (pinfunction "VSS_G12") (pintype "passive"))
      (node (ref "U9") (pin "G2") (pinfunction "VSS_G2") (pintype "passive"))
      (node (ref "U9") (pin "G6") (pinfunction "VSS_G6") (pintype "passive"))
      (node (ref "U9") (pin "G7") (pinfunction "VSS_G7") (pintype "passive"))
      (node (ref "U9") (pin "G8") (pinfunction "VSS_G8") (pintype "passive"))
      (node (ref "U9") (pin "G9") (pinfunction "VSS_G9") (pintype "passive"))
      (node (ref "U9") (pin "H10") (pinfunction "VSS_H10") (pintype "passive"))
      (node (ref "U9") (pin "H12") (pinfunction "VSS_H12") (pintype "passive"))
      (node (ref "U9") (pin "H6") (pinfunction "VSS_H6") (pintype "passive"))
      (node (ref "U9") (pin "H7") (pinfunction "VSS_H7") (pintype "passive"))
      (node (ref "U9") (pin "H8") (pinfunction "VSS_H8") (pintype "passive"))
      (node (ref "U9") (pin "H9") (pinfunction "VSS_H9") (pintype "passive"))
      (node (ref "U9") (pin "J10") (pinfunction "VSS_J10") (pintype "passive"))
      (node (ref "U9") (pin "J6") (pinfunction "VSS_J6") (pintype "passive"))
      (node (ref "U9") (pin "J7") (pinfunction "VSS_J7") (pintype "passive"))
      (node (ref "U9") (pin "J8") (pinfunction "VSS_J8") (pintype "passive"))
      (node (ref "U9") (pin "J9") (pinfunction "VSS_J9") (pintype "passive"))
      (node (ref "U9") (pin "K10") (pinfunction "VSS_K10") (pintype "passive"))
      (node (ref "U9") (pin "K6") (pinfunction "VSS_K6") (pintype "passive"))
      (node (ref "U9") (pin "K7") (pinfunction "VSS_K7") (pintype "passive"))
      (node (ref "U9") (pin "K8") (pinfunction "VSS_K8") (pintype "passive"))
      (node (ref "U9") (pin "K9") (pinfunction "VSS_K9") (pintype "passive"))
      (node (ref "U9") (pin "M1") (pinfunction "VSSA_M1") (pintype "passive"))
      (node (ref "U9") (pin "M8") (pinfunction "VSS_M8") (pintype "passive"))
      (node (ref "U9") (pin "M9") (pinfunction "VSS_M9") (pintype "passive"))
      (node (ref "U9") (pin "N1") (pinfunction "VREF-_N1") (pintype "passive"))
      (node (ref "X1") (pin "2") (pinfunction "GND_2") (pintype "passive"))
    )
    (net (code "38") (name "Net-(D10-A)") (class "Default")
      (node (ref "D10") (pin "1") (pinfunction "A_1") (pintype "passive"))
      (node (ref "SB31") (pin "2") (pinfunction "2_2") (pintype "passive"))
    )
    (net (code "39") (name "Net-(D10-K)") (class "Default")
      (node (ref "C42") (pin "2") (pinfunction "2_2") (pintype "passive"))
      (node (ref "C43") (pin "2") (pinfunction "2_2") (pintype "passive"))
      (node (ref "D10") (pin "2") (pinfunction "K_2") (pintype "passive"))
      (node (ref "D11") (pin "2") (pinfunction "K_2") (pintype "passive"))
      (node (ref "D9") (pin "2") (pinfunction "K_2") (pintype "passive"))
      (node (ref "U5") (pin "1") (pinfunction "Vin_1") (pintype "passive"))
      (node (ref "U5") (pin "3") (pinfunction "CE_3") (pintype "passive"))
    )
    (net (code "40") (name "Net-(JP7-NO)") (class "Default")
      (node (ref "JP7") (pin "2") (pinfunction "NO_2") (pintype "passive"))
      (node (ref "R115") (pin "1") (pinfunction "1_1") (pintype "passive"))
    )
    (net (code "41") (name "Net-(LD8-Pad1)") (class "Default")
      (node (ref "LD8") (pin "1") (pintype "passive"))
      (node (ref "R121") (pin "1") (pinfunction "1_1") (pintype "passive"))
    )
    (net (code "42") (name "Net-(LD9-Red_anode)") (class "Default")
      (node (ref "LD9") (pin "2") (pinfunction "Red_anode_2") (pintype "passive"))
      (node (ref "R129") (pin "1") (pinfunction "1_1") (pintype "passive"))
    )
    (net (code "43") (name "Net-(LD9-YellowGreen_cathode)") (class "Default")
      (node (ref "LD9") (pin "3") (pinfunction "YellowGreen_cathode_3") (pintype "passive"))
      (node (ref "R128") (pin "1") (pinfunction "1_1") (pintype "passive"))
    )
    (net (code "44") (name "Net-(R105-Pad1)") (class "Default")
      (node (ref "R105") (pin "1") (pinfunction "1_1") (pintype "passive"))
      (node (ref "SW1") (pin "4") (pinfunction "4_4") (pintype "passive"))
    )
    (net (code "45") (name "Net-(R111-Pad1)") (class "Default")
      (node (ref "R111") (pin "1") (pinfunction "1_1") (pintype "passive"))
      (node (ref "SW1") (pin "8") (pinfunction "8_8") (pintype "passive"))
    )
    (net (code "46") (name "Net-(R112-Pad1)") (class "Default")
      (node (ref "R112") (pin "1") (pinfunction "1_1") (pintype "passive"))
      (node (ref "SW1") (pin "7") (pinfunction "7_7") (pintype "passive"))
    )
    (net (code "47") (name "Net-(R113-Pad1)") (class "Default")
      (node (ref "R113") (pin "1") (pinfunction "1_1") (pintype "passive"))
      (node (ref "SW1") (pin "6") (pinfunction "6_6") (pintype "passive"))
    )
    (net (code "48") (name "Net-(R114-Pad1)") (class "Default")
      (node (ref "R114") (pin "1") (pinfunction "1_1") (pintype "passive"))
      (node (ref "SW1") (pin "5") (pinfunction "5_5") (pintype "passive"))
    )
    (net (code "49") (name "Net-(R124-Pad2)") (class "Default")
      (node (ref "R124") (pin "2") (pinfunction "2_2") (pintype "passive"))
      (node (ref "R125") (pin "2") (pinfunction "2_2") (pintype "passive"))
      (node (ref "SW1") (pin "1") (pinfunction "1_1") (pintype "passive"))
    )
    (net (code "50") (name "Net-(R126-Pad1)") (class "Default")
      (node (ref "R126") (pin "1") (pinfunction "1_1") (pintype "passive"))
      (node (ref "R127") (pin "1") (pinfunction "1_1") (pintype "passive"))
      (node (ref "SW1") (pin "2") (pinfunction "2_2") (pintype "passive"))
    )
    (net (code "51") (name "Net-(U5-BYPASS)") (class "Default")
      (node (ref "C44") (pin "2") (pinfunction "2_2") (pintype "passive"))
      (node (ref "U5") (pin "4") (pinfunction "BYPASS_4") (pintype "passive"))
    )
    (net (code "52") (name "Net-(U9A-BOOT0)") (class "Default")
      (node (ref "R120") (pin "2") (pinfunction "2_2") (pintype "passive"))
      (node (ref "U9") (pin "D6") (pinfunction "BOOT0_D6") (pintype "passive"))
    )
    (net (code "53") (name "Net-(U9A-PDR_ON)") (class "Default")
      (node (ref "R123") (pin "2") (pinfunction "2_2") (pintype "passive"))
      (node (ref "U9") (pin "C6") (pinfunction "PDR_ON_C6") (pintype "passive"))
    )
    (net (code "54") (name "Net-(U9A-REXT_OTGPHY)") (class "Default")
      (node (ref "R131") (pin "2") (pinfunction "2_2") (pintype "passive"))
      (node (ref "U9") (pin "J15") (pinfunction "REXT_OTGPHY_J15") (pintype "passive"))
    )
    (net (code "55") (name "Net-(U9A-V12_OTGPHY)") (class "Default")
      (node (ref "C82") (pin "2") (pinfunction "2_2") (pintype "passive"))
      (node (ref "U9") (pin "J14") (pinfunction "V12_OTGPHY_J14") (pintype "passive"))
    )
    (net (code "56") (name "Net-(U9B-BYPASS-REG)") (class "Default")
      (node (ref "R118") (pin "2") (pinfunction "2_2") (pintype "passive"))
      (node (ref "U9") (pin "L4") (pinfunction "BYPASS-REG_L4") (pintype "passive"))
    )
    (net (code "57") (name "Net-(U9B-VCAP1)") (class "Default")
      (node (ref "C74") (pin "2") (pinfunction "2_2") (pintype "passive"))
      (node (ref "U9") (pin "M10") (pinfunction "VCAP1_M10") (pintype "passive"))
    )
    (net (code "58") (name "Net-(U9B-VCAP2)") (class "Default")
      (node (ref "C78") (pin "2") (pinfunction "2_2") (pintype "passive"))
      (node (ref "U9") (pin "F13") (pinfunction "VCAP2_F13") (pintype "passive"))
    )
    (net (code "59") (name "Net-(U10-~{FAULT})") (class "Default")
      (node (ref "LD8") (pin "2") (pintype "passive"))
      (node (ref "R119") (pin "1") (pinfunction "1_1") (pintype "passive"))
      (node (ref "U10") (pin "3") (pinfunction "~{FAULT}_3") (pintype "passive"))
    )
    (net (code "60") (name "Net-(X1-EN)") (class "Default")
      (node (ref "R116") (pin "2") (pinfunction "2_2") (pintype "passive"))
      (node (ref "X1") (pin "1") (pinfunction "EN_1") (pintype "passive"))
    )
    (net (code "61") (name "Net-(X1-OUT)") (class "Default")
      (node (ref "R117") (pin "1") (pinfunction "1_1") (pintype "passive"))
      (node (ref "X1") (pin "3") (pinfunction "OUT_3") (pintype "passive"))
    )
    (net (code "62") (name "unconnected-(CN1-Pad1)") (class "Default")
      (node (ref "CN1") (pin "1") (pinfunction "1_1") (pintype "passive+no_connect"))
    )
    (net (code "63") (name "unconnected-(CN1-Pad2)") (class "Default")
      (node (ref "CN1") (pin "2") (pinfunction "2_2") (pintype "passive+no_connect"))
    )
    (net (code "64") (name "unconnected-(CN1-Pad9)") (class "Default")
      (node (ref "CN1") (pin "9") (pinfunction "9_9") (pintype "passive+no_connect"))
    )
    (net (code "65") (name "unconnected-(CN3-ID-Pad4)") (class "Default")
      (node (ref "CN3") (pin "4") (pinfunction "ID_4") (pintype "passive+no_connect"))
    )
    (net (code "66") (name "unconnected-(CN10-Pad1)") (class "Default")
      (node (ref "CN10") (pin "1") (pinfunction "1_1") (pintype "passive+no_connect"))
    )
    (net (code "67") (name "unconnected-(CN10-Pad7)") (class "Default")
      (node (ref "CN10") (pin "7") (pinfunction "7_7") (pintype "passive+no_connect"))
    )
    (net (code "68") (name "unconnected-(CN10-Pad8)") (class "Default")
      (node (ref "CN10") (pin "8") (pinfunction "8_8") (pintype "passive+no_connect"))
    )
    (net (code "69") (name "unconnected-(CN10-Pad9)") (class "Default")
      (node (ref "CN10") (pin "9") (pinfunction "9_9") (pintype "passive+no_connect"))
    )
    (net (code "70") (name "unconnected-(U9A-HW_TYP_0{slash}PI4-PadD4)") (class "Default")
      (node (ref "U9") (pin "D4") (pinfunction "HW_TYP_0/PI4_D4") (pintype "passive+no_connect"))
    )
    (net (code "71") (name "unconnected-(U9A-HW_TYP_1{slash}PI5-PadC4)") (class "Default")
      (node (ref "U9") (pin "C4") (pinfunction "HW_TYP_1/PI5_C4") (pintype "passive+no_connect"))
    )
    (net (code "72") (name "unconnected-(U9A-OSC_OUT{slash}PH1-PadH1)") (class "Default")
      (node (ref "U9") (pin "H1") (pinfunction "OSC_OUT/PH1_H1") (pintype "passive+no_connect"))
    )
    (net (code "73") (name "unconnected-(U9A-T_SW_DIR{slash}PA7-PadR3)") (class "Default")
      (node (ref "U9") (pin "R3") (pinfunction "T_SW_DIR/PA7_R3") (pintype "passive+no_connect"))
    )
    (net (code "74") (name "unconnected-(U15-NC-Pad4)") (class "Default")
      (node (ref "U15") (pin "4") (pinfunction "NC_4") (pintype "passive+no_connect"))
    )
  )
)
